# 5V_AC_TO_DC.net
KiCad netlist of a schematic drawn in EAGLE
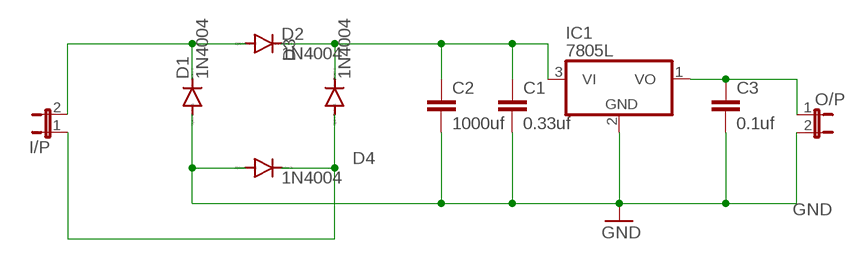
[diagram p0: schematic, sheet 1]

(export (version "E")
  (design (tool "Eeschema 10.0.6"))
  (components
    (comp (ref "C1")
      (value "0.33uf")
      (footprint "eagle-import:C2.5-3")
      (libsource (lib "eagle-import") (part "C2,5-3"))
    )
    (comp (ref "C2")
      (value "1000uf")
      (footprint "eagle-import:C2.5-3")
      (libsource (lib "eagle-import") (part "C2,5-3"))
    )
    (comp (ref "C3")
      (value "0.1uf")
      (footprint "eagle-import:C2.5-3")
      (libsource (lib "eagle-import") (part "C2,5-3"))
    )
    (comp (ref "D1")
      (value "1N4004")
      (footprint "eagle-import:DO41-10")
      (libsource (lib "eagle-import") (part "1N4004"))
    )
    (comp (ref "D2")
      (value "1N4004")
      (footprint "eagle-import:DO41-10")
      (libsource (lib "eagle-import") (part "1N4004"))
    )
    (comp (ref "D3")
      (value "1N4004")
      (footprint "eagle-import:DO41-10")
      (libsource (lib "eagle-import") (part "1N4004"))
    )
    (comp (ref "D4")
      (value "1N4004")
      (footprint "eagle-import:DO41-10")
      (libsource (lib "eagle-import") (part "1N4004"))
    )
    (comp (ref "I/P")
      (value "JP1E")
      (footprint "eagle-import:JP1")
      (libsource (lib "eagle-import") (part "JP1E"))
    )
    (comp (ref "IC1")
      (value "7805L")
      (footprint "eagle-import:TO92")
      (libsource (lib "eagle-import") (part "78L05"))
    )
    (comp (ref "O/P")
      (value "JP1E")
      (footprint "eagle-import:JP1")
      (libsource (lib "eagle-import") (part "JP1E"))
    )
  )
  (nets
    (net (code "1") (name "GND") (class "Default")
      (node (ref "C1") (pin "2") (pinfunction "2_2") (pintype "passive"))
      (node (ref "C2") (pin "2") (pinfunction "2_2") (pintype "passive"))
      (node (ref "C3") (pin "2") (pinfunction "2_2") (pintype "passive"))
      (node (ref "D1") (pin "A") (pinfunction "A_A") (pintype "passive"))
      (node (ref "D4") (pin "A") (pinfunction "A_A") (pintype "passive"))
      (node (ref "IC1") (pin "2") (pinfunction "GND_2") (pintype "passive"))
      (node (ref "O/P") (pin "2") (pinfunction "2_2") (pintype "passive"))
    )
    (net (code "2") (name "Net-(D1-PadC)") (class "Default")
      (node (ref "D1") (pin "C") (pinfunction "C_C") (pintype "passive"))
      (node (ref "D2") (pin "A") (pinfunction "A_A") (pintype "passive"))
      (node (ref "I/P") (pin "2") (pinfunction "2_2") (pintype "passive"))
    )
    (net (code "3") (name "Net-(D3-PadA)") (class "Default")
      (node (ref "D3") (pin "A") (pinfunction "A_A") (pintype "passive"))
      (node (ref "D4") (pin "C") (pinfunction "C_C") (pintype "passive"))
      (node (ref "I/P") (pin "1") (pinfunction "1_1") (pintype "passive"))
    )
    (net (code "4") (name "Net-(IC1-VI)") (class "Default")
      (node (ref "C1") (pin "1") (pinfunction "1_1") (pintype "passive"))
      (node (ref "C2") (pin "1") (pinfunction "1_1") (pintype "passive"))
      (node (ref "D2") (pin "C") (pinfunction "C_C") (pintype "passive"))
      (node (ref "D3") (pin "C") (pinfunction "C_C") (pintype "passive"))
      (node (ref "IC1") (pin "3") (pinfunction "VI_3") (pintype "input"))
    )
    (net (code "5") (name "Net-(IC1-VO)") (class "Default")
      (node (ref "C3") (pin "1") (pinfunction "1_1") (pintype "passive"))
      (node (ref "IC1") (pin "1") (pinfunction "VO_1") (pintype "passive"))
      (node (ref "O/P") (pin "1") (pinfunction "1_1") (pintype "passive"))
    )
  )
)
